# HDN_Management.net
KiCad netlist of a schematic drawn in Altium Designer
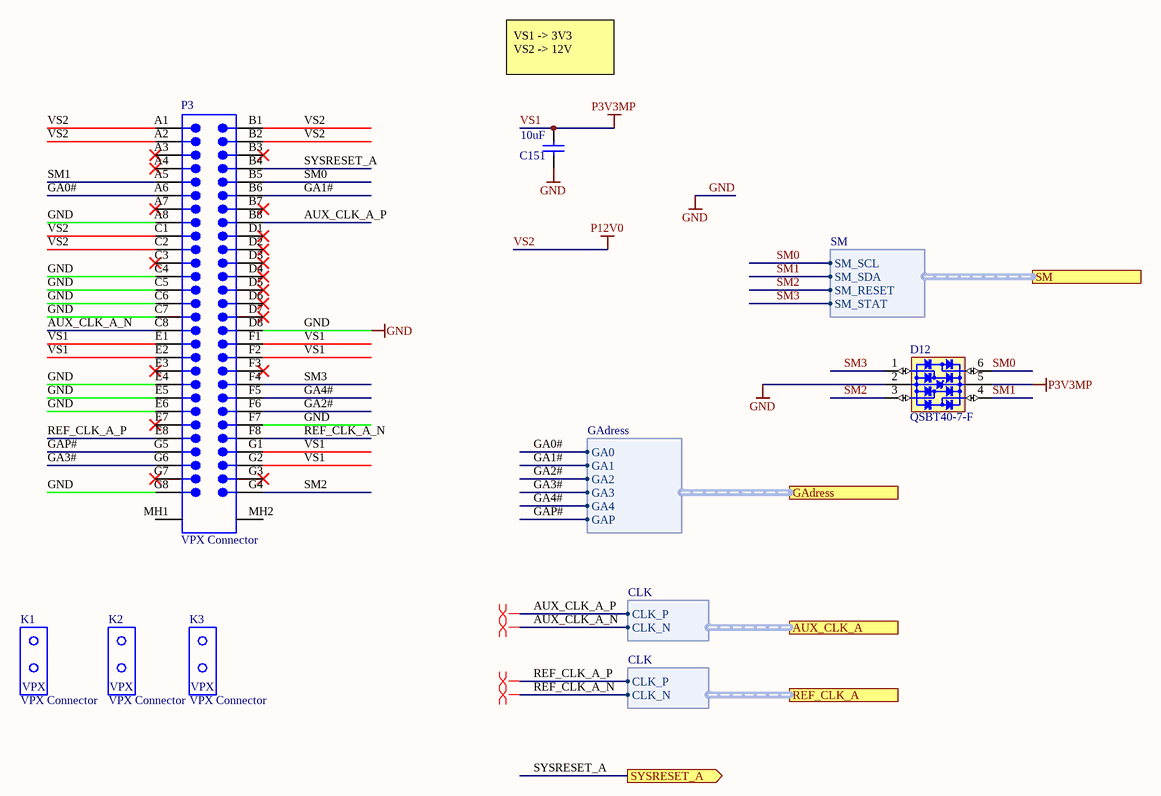
[diagram p0: HDN_Management.SchDoc]

(export (version "E")
  (design (tool "Eeschema 10.0.6"))
  (components
    (comp (ref "C151")
      (value "10uF")
      (footprint "CAPC2012X135N")
      (description "Non-polarised capacitor")
      (fields
        (field (name "PART NUMBER") "CC0805_10UF_16V_10%_X5R")
        (field (name "VOLTAGE") "16V")
        (field (name "AUTHOR") "CERN DEM JLC")
      )
      (libsource (lib "Capacitors") (part "Capacitor - non polarized"))
    )
    (comp (ref "D12")
      (value "QSBT40-7-F")
      (footprint "SOT65P210X110-6N")
      (libsource (lib "LIBRARY_SCH") (part "D_TVS_QSBT40-7-F"))
    )
    (comp (ref "K1")
      (value "VPX Connector")
      (footprint "BTB5-5-2H2F")
      (description "VPX VITA 46 Alignment key, Right Angle, 1Key, Key orientation 0")
      (fields (field (name "MANUFACTURER") "TE") (field (name "MANUFACTURER PART NUMBER") "1469492-1"))
      (libsource (lib "LIBRARY_SCH") (part "CON_VPX_1469492-1"))
    )
    (comp (ref "K2")
      (value "VPX Connector")
      (footprint "BTB5-5-2H2F")
      (description "VPX VITA 46 Alignment key, Right Angle, 1Key, Key orientation 0")
      (fields (field (name "MANUFACTURER") "TE") (field (name "MANUFACTURER PART NUMBER") "1469492-1"))
      (libsource (lib "LIBRARY_SCH") (part "CON_VPX_1469492-1"))
    )
    (comp (ref "K3")
      (value "VPX Connector")
      (footprint "BTB5-5-2H2F")
      (description "VPX VITA 46 Alignment key, Right Angle, 1Key, Key orientation 0")
      (fields (field (name "MANUFACTURER") "TE") (field (name "MANUFACTURER PART NUMBER") "1469492-1"))
      (libsource (lib "LIBRARY_SCH") (part "CON_VPX_1469492-1"))
    )
    (comp (ref "P3")
      (value "VPX Connector")
      (footprint "BTB1-8-2H56M")
      (description "Board-to-Board Connector, Right Angle, 7-Row, Pitch 1.8mm, 56-Position")
      (fields (field (name "MANUFACTURER") "TE") (field (name "MANUFACTURER PART NUMBER") "1410189-3"))
      (libsource (lib "LIBRARY_SCH") (part "CON_VPX_1410189-3"))
    )
  )
  (nets
    (net (code "4") (name "/AUX_CLK_A_N") (class "Default")
      (node (ref "P3") (pin "C8") (pinfunction "C8_C8") (pintype "passive"))
    )
    (net (code "5") (name "/AUX_CLK_A_P") (class "Default")
      (node (ref "P3") (pin "B8") (pinfunction "B8_B8") (pintype "passive"))
    )
    (net (code "6") (name "/GA0#") (class "Default")
      (node (ref "P3") (pin "A6") (pinfunction "A6_A6") (pintype "passive"))
    )
    (net (code "7") (name "/GA1#") (class "Default")
      (node (ref "P3") (pin "B6") (pinfunction "B6_B6") (pintype "passive"))
    )
    (net (code "8") (name "/GA2#") (class "Default")
      (node (ref "P3") (pin "F6") (pinfunction "F6_F6") (pintype "passive"))
    )
    (net (code "9") (name "/GA3#") (class "Default")
      (node (ref "P3") (pin "G6") (pinfunction "G6_G6") (pintype "passive"))
    )
    (net (code "10") (name "/GA4#") (class "Default")
      (node (ref "P3") (pin "F5") (pinfunction "F5_F5") (pintype "passive"))
    )
    (net (code "11") (name "/GAP#") (class "Default")
      (node (ref "P3") (pin "G5") (pinfunction "G5_G5") (pintype "passive"))
    )
    (net (code "12") (name "/REF_CLK_A_N") (class "Default")
      (node (ref "P3") (pin "F8") (pinfunction "F8_F8") (pintype "passive"))
    )
    (net (code "13") (name "/REF_CLK_A_P") (class "Default")
      (node (ref "P3") (pin "E8") (pinfunction "E8_E8") (pintype "passive"))
    )
    (net (code "14") (name "/SM0") (class "Default")
      (node (ref "D12") (pin "6") (pinfunction "I/O4_6") (pintype "bidirectional"))
      (node (ref "P3") (pin "B5") (pinfunction "B5_B5") (pintype "passive"))
    )
    (net (code "15") (name "/SM1") (class "Default")
      (node (ref "D12") (pin "4") (pinfunction "I/O3_4") (pintype "bidirectional"))
      (node (ref "P3") (pin "A5") (pinfunction "A5_A5") (pintype "passive"))
    )
    (net (code "16") (name "/SM2") (class "Default")
      (node (ref "D12") (pin "3") (pinfunction "I/O2_3") (pintype "bidirectional"))
      (node (ref "P3") (pin "G4") (pinfunction "G4_G4") (pintype "passive"))
    )
    (net (code "17") (name "/SM3") (class "Default")
      (node (ref "D12") (pin "1") (pinfunction "I/O1_1") (pintype "bidirectional"))
      (node (ref "P3") (pin "F4") (pinfunction "F4_F4") (pintype "passive"))
    )
    (net (code "18") (name "/SYSRESET_A") (class "Default")
      (node (ref "P3") (pin "B4") (pinfunction "B4_B4") (pintype "passive"))
    )
    (net (code "22") (name "GND") (class "Default")
      (node (ref "C151") (pin "1") (pinfunction "1_1") (pintype "passive"))
      (node (ref "D12") (pin "2") (pinfunction "GND_2") (pintype "power_in"))
      (node (ref "P3") (pin "A8") (pinfunction "A8_A8") (pintype "passive"))
      (node (ref "P3") (pin "C4") (pinfunction "C4_C4") (pintype "passive"))
      (node (ref "P3") (pin "C5") (pinfunction "C5_C5") (pintype "passive"))
      (node (ref "P3") (pin "C6") (pinfunction "C6_C6") (pintype "passive"))
      (node (ref "P3") (pin "C7") (pinfunction "C7_C7") (pintype "passive"))
      (node (ref "P3") (pin "D8") (pinfunction "D8_D8") (pintype "passive"))
      (node (ref "P3") (pin "E4") (pinfunction "E4_E4") (pintype "passive"))
      (node (ref "P3") (pin "E5") (pinfunction "E5_E5") (pintype "passive"))
      (node (ref "P3") (pin "E6") (pinfunction "E6_E6") (pintype "passive"))
      (node (ref "P3") (pin "F7") (pinfunction "F7_F7") (pintype "passive"))
      (node (ref "P3") (pin "G8") (pinfunction "G8_G8") (pintype "passive"))
    )
    (net (code "23") (name "P3V3MP") (class "Default")
      (node (ref "C151") (pin "2") (pinfunction "2_2") (pintype "passive"))
      (node (ref "D12") (pin "5") (pinfunction "VBUS_5") (pintype "power_in"))
      (node (ref "P3") (pin "E1") (pinfunction "E1_E1") (pintype "passive"))
      (node (ref "P3") (pin "E2") (pinfunction "E2_E2") (pintype "passive"))
      (node (ref "P3") (pin "F1") (pinfunction "F1_F1") (pintype "passive"))
      (node (ref "P3") (pin "F2") (pinfunction "F2_F2") (pintype "passive"))
      (node (ref "P3") (pin "G1") (pinfunction "G1_G1") (pintype "passive"))
      (node (ref "P3") (pin "G2") (pinfunction "G2_G2") (pintype "passive"))
    )
    (net (code "24") (name "P12V0") (class "Default")
      (node (ref "P3") (pin "A1") (pinfunction "A1_A1") (pintype "passive"))
      (node (ref "P3") (pin "A2") (pinfunction "A2_A2") (pintype "passive"))
      (node (ref "P3") (pin "B1") (pinfunction "B1_B1") (pintype "passive"))
      (node (ref "P3") (pin "B2") (pinfunction "B2_B2") (pintype "passive"))
      (node (ref "P3") (pin "C1") (pinfunction "C1_C1") (pintype "passive"))
      (node (ref "P3") (pin "C2") (pinfunction "C2_C2") (pintype "passive"))
    )
    (net (code "25") (name "unconnected-(P3-PadA3)") (class "Default")
      (node (ref "P3") (pin "A3") (pinfunction "A3_A3") (pintype "passive+no_connect"))
    )
    (net (code "26") (name "unconnected-(P3-PadA4)") (class "Default")
      (node (ref "P3") (pin "A4") (pinfunction "A4_A4") (pintype "passive+no_connect"))
    )
    (net (code "27") (name "unconnected-(P3-PadA7)") (class "Default")
      (node (ref "P3") (pin "A7") (pinfunction "A7_A7") (pintype "passive+no_connect"))
    )
    (net (code "28") (name "unconnected-(P3-PadB3)") (class "Default")
      (node (ref "P3") (pin "B3") (pinfunction "B3_B3") (pintype "passive+no_connect"))
    )
    (net (code "29") (name "unconnected-(P3-PadB7)") (class "Default")
      (node (ref "P3") (pin "B7") (pinfunction "B7_B7") (pintype "passive+no_connect"))
    )
    (net (code "30") (name "unconnected-(P3-PadC3)") (class "Default")
      (node (ref "P3") (pin "C3") (pinfunction "C3_C3") (pintype "passive+no_connect"))
    )
    (net (code "31") (name "unconnected-(P3-PadD1)") (class "Default")
      (node (ref "P3") (pin "D1") (pinfunction "D1_D1") (pintype "passive+no_connect"))
    )
    (net (code "32") (name "unconnected-(P3-PadD2)") (class "Default")
      (node (ref "P3") (pin "D2") (pinfunction "D2_D2") (pintype "passive+no_connect"))
    )
    (net (code "33") (name "unconnected-(P3-PadD3)") (class "Default")
      (node (ref "P3") (pin "D3") (pinfunction "D3_D3") (pintype "passive+no_connect"))
    )
    (net (code "34") (name "unconnected-(P3-PadD4)") (class "Default")
      (node (ref "P3") (pin "D4") (pinfunction "D4_D4") (pintype "passive+no_connect"))
    )
    (net (code "35") (name "unconnected-(P3-PadD5)") (class "Default")
      (node (ref "P3") (pin "D5") (pinfunction "D5_D5") (pintype "passive+no_connect"))
    )
    (net (code "36") (name "unconnected-(P3-PadD6)") (class "Default")
      (node (ref "P3") (pin "D6") (pinfunction "D6_D6") (pintype "passive+no_connect"))
    )
    (net (code "37") (name "unconnected-(P3-PadD7)") (class "Default")
      (node (ref "P3") (pin "D7") (pinfunction "D7_D7") (pintype "passive+no_connect"))
    )
    (net (code "38") (name "unconnected-(P3-PadE3)") (class "Default")
      (node (ref "P3") (pin "E3") (pinfunction "E3_E3") (pintype "passive+no_connect"))
    )
    (net (code "39") (name "unconnected-(P3-PadE7)") (class "Default")
      (node (ref "P3") (pin "E7") (pinfunction "E7_E7") (pintype "passive+no_connect"))
    )
    (net (code "40") (name "unconnected-(P3-PadF3)") (class "Default")
      (node (ref "P3") (pin "F3") (pinfunction "F3_F3") (pintype "passive+no_connect"))
    )
    (net (code "41") (name "unconnected-(P3-PadG3)") (class "Default")
      (node (ref "P3") (pin "G3") (pinfunction "G3_G3") (pintype "passive+no_connect"))
    )
    (net (code "42") (name "unconnected-(P3-PadG7)") (class "Default")
      (node (ref "P3") (pin "G7") (pinfunction "G7_G7") (pintype "passive+no_connect"))
    )
    (net (code "43") (name "unconnected-(P3-PadMH1)") (class "Default")
      (node (ref "P3") (pin "MH1") (pinfunction "MH1_MH1") (pintype "passive"))
    )
    (net (code "44") (name "unconnected-(P3-PadMH2)") (class "Default")
      (node (ref "P3") (pin "MH2") (pinfunction "MH2_MH2") (pintype "passive"))
    )
  )
)
